# Differential_voltage_input.net
KiCad netlist of a schematic drawn in Altium Designer
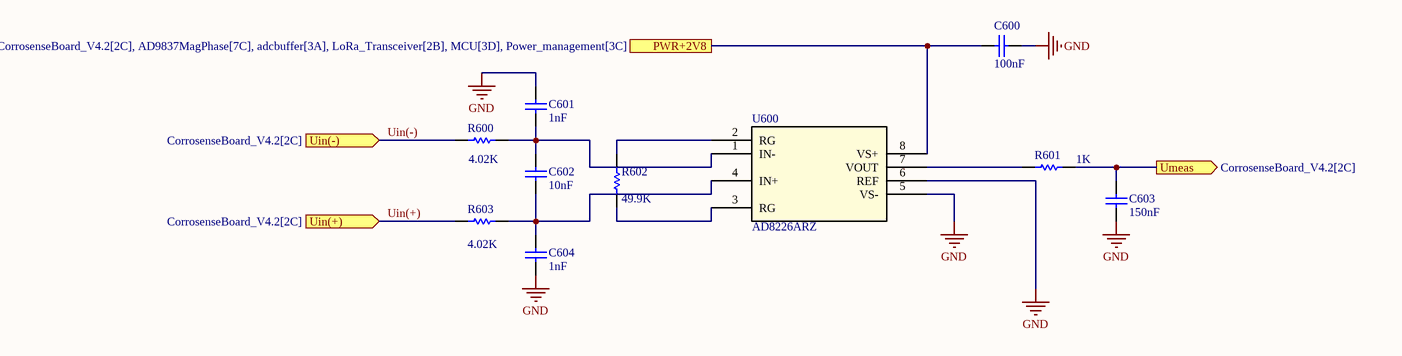
[diagram p0: Differential_voltage_input.SchDoc]

(export (version "E")
  (design (tool "Eeschema 10.0.6"))
  (components
    (comp (ref "C600")
      (value "100nF")
      (footprint "1608[0603]")
      (description "CAP CER 25V X7R 0603")
      (fields (field (name "TOLERANCE") "±10%") (field (name "MANUFACTURER") "Murata Electronics"))
      (libsource (lib "Miscellaneous Devices") (part "Cap"))
    )
    (comp (ref "C601")
      (value "1nF")
      (footprint "1608[0603]")
      (description "CAP CER 25V X7R 0603")
      (fields (field (name "TOLERANCE") "±10%") (field (name "MANUFACTURER") "KYOCERA AVX"))
      (libsource (lib "Miscellaneous Devices") (part "Cap"))
    )
    (comp (ref "C602")
      (value "10nF")
      (footprint "1608[0603]")
      (description "CAP CER 25V X7R 0603")
      (fields (field (name "TOLERANCE") "±10%") (field (name "MANUFACTURER") "Murata Electronics"))
      (libsource (lib "Miscellaneous Devices") (part "Cap"))
    )
    (comp (ref "C603")
      (value "150nF")
      (footprint "1608[0603]")
      (description "CAP CER 25V X7R 0603")
      (fields (field (name "TOLERANCE") "±10%") (field (name "MANUFACTURER") "Murata Electronics"))
      (libsource (lib "Miscellaneous Devices") (part "Cap"))
    )
    (comp (ref "C604")
      (value "1nF")
      (footprint "1608[0603]")
      (description "CAP CER 25V X7R 0603")
      (fields (field (name "TOLERANCE") "±10%") (field (name "MANUFACTURER") "KYOCERA AVX"))
      (libsource (lib "Miscellaneous Devices") (part "Cap"))
    )
    (comp (ref "R600")
      (value "4.02K")
      (footprint "1608[0603]")
      (description "RES SMD 2% 1.5W 0603")
      (fields
        (field (name "MP") "-65°C ~ 155°C")
        (field (name "TOLERANCE") "2%")
        (field (name "PUBLISHER") "Altium Limited")
      )
      (libsource (lib "Res1") (part "Res1"))
    )
    (comp (ref "R601")
      (value "1K")
      (footprint "1608[0603]")
      (description "RES SMD 2% 1.5W 0603")
      (fields
        (field (name "MP") "-65°C ~ 155°C")
        (field (name "TOLERANCE") "2%")
        (field (name "PUBLISHER") "Altium Limited")
      )
      (libsource (lib "Res1") (part "Res1"))
    )
    (comp (ref "R602")
      (value "49.9K")
      (footprint "1608[0603]")
      (description "RES SMD 2% 1.5W 0603")
      (fields
        (field (name "MP") "-65°C ~ 155°C")
        (field (name "TOLERANCE") "2%")
        (field (name "PUBLISHER") "Altium Limited")
      )
      (libsource (lib "Res1") (part "Res1"))
    )
    (comp (ref "R603")
      (value "4.02K")
      (footprint "1608[0603]")
      (description "RES SMD 2% 1.5W 0603")
      (fields
        (field (name "MP") "-65°C ~ 155°C")
        (field (name "TOLERANCE") "2%")
        (field (name "PUBLISHER") "Altium Limited")
      )
      (libsource (lib "Res1") (part "Res1"))
    )
    (comp (ref "U600")
      (value "AD8226ARZ")
      (footprint "SOIC127P600X175-8N")
      (description "No Description Available")
      (fields (field (name "MANUFACTURER") "Analog Devices Inc"))
      (libsource (lib "AD8226ARZ") (part "AD8226ARZ"))
    )
  )
  (nets
    (net (code "1") (name "/PWR+2V8") (class "Default")
      (node (ref "C600") (pin "1") (pinfunction "1_1") (pintype "passive"))
      (node (ref "U600") (pin "8") (pinfunction "VS+_8") (pintype "power_in"))
    )
    (net (code "2") (name "/Uin(+)") (class "Default")
      (node (ref "R603") (pin "1") (pinfunction "1_1") (pintype "passive"))
    )
    (net (code "3") (name "/Uin(-)") (class "Default")
      (node (ref "R600") (pin "1") (pinfunction "1_1") (pintype "passive"))
    )
    (net (code "4") (name "/Umeas") (class "Default")
      (node (ref "C603") (pin "1") (pinfunction "1_1") (pintype "passive"))
      (node (ref "R601") (pin "2") (pinfunction "2_2") (pintype "passive"))
    )
    (net (code "5") (name "GND") (class "Default")
      (node (ref "C600") (pin "2") (pinfunction "2_2") (pintype "passive"))
      (node (ref "C601") (pin "1") (pinfunction "1_1") (pintype "passive"))
      (node (ref "C603") (pin "2") (pinfunction "2_2") (pintype "passive"))
      (node (ref "C604") (pin "2") (pinfunction "2_2") (pintype "passive"))
      (node (ref "U600") (pin "5") (pinfunction "VS-_5") (pintype "power_in"))
      (node (ref "U600") (pin "6") (pinfunction "REF_6") (pintype "passive"))
    )
    (net (code "6") (name "Net-(R602-Pad1)") (class "Default")
      (node (ref "R602") (pin "1") (pinfunction "1_1") (pintype "passive"))
      (node (ref "U600") (pin "3") (pinfunction "RG_3") (pintype "passive"))
    )
    (net (code "7") (name "Net-(R602-Pad2)") (class "Default")
      (node (ref "R602") (pin "2") (pinfunction "2_2") (pintype "passive"))
      (node (ref "U600") (pin "2") (pinfunction "RG_2") (pintype "passive"))
    )
    (net (code "8") (name "Net-(U600-IN+)") (class "Default")
      (node (ref "C602") (pin "2") (pinfunction "2_2") (pintype "passive"))
      (node (ref "C604") (pin "1") (pinfunction "1_1") (pintype "passive"))
      (node (ref "R603") (pin "2") (pinfunction "2_2") (pintype "passive"))
      (node (ref "U600") (pin "4") (pinfunction "IN+_4") (pintype "passive"))
    )
    (net (code "9") (name "Net-(U600-IN-)") (class "Default")
      (node (ref "C601") (pin "2") (pinfunction "2_2") (pintype "passive"))
      (node (ref "C602") (pin "1") (pinfunction "1_1") (pintype "passive"))
      (node (ref "R600") (pin "2") (pinfunction "2_2") (pintype "passive"))
      (node (ref "U600") (pin "1") (pinfunction "IN-_1") (pintype "passive"))
    )
    (net (code "10") (name "Net-(U600-VOUT)") (class "Default")
      (node (ref "R601") (pin "1") (pinfunction "1_1") (pintype "passive"))
      (node (ref "U600") (pin "7") (pinfunction "VOUT_7") (pintype "passive"))
    )
  )
)
